# example_led.net
KiCad netlist of a schematic drawn in EAGLE
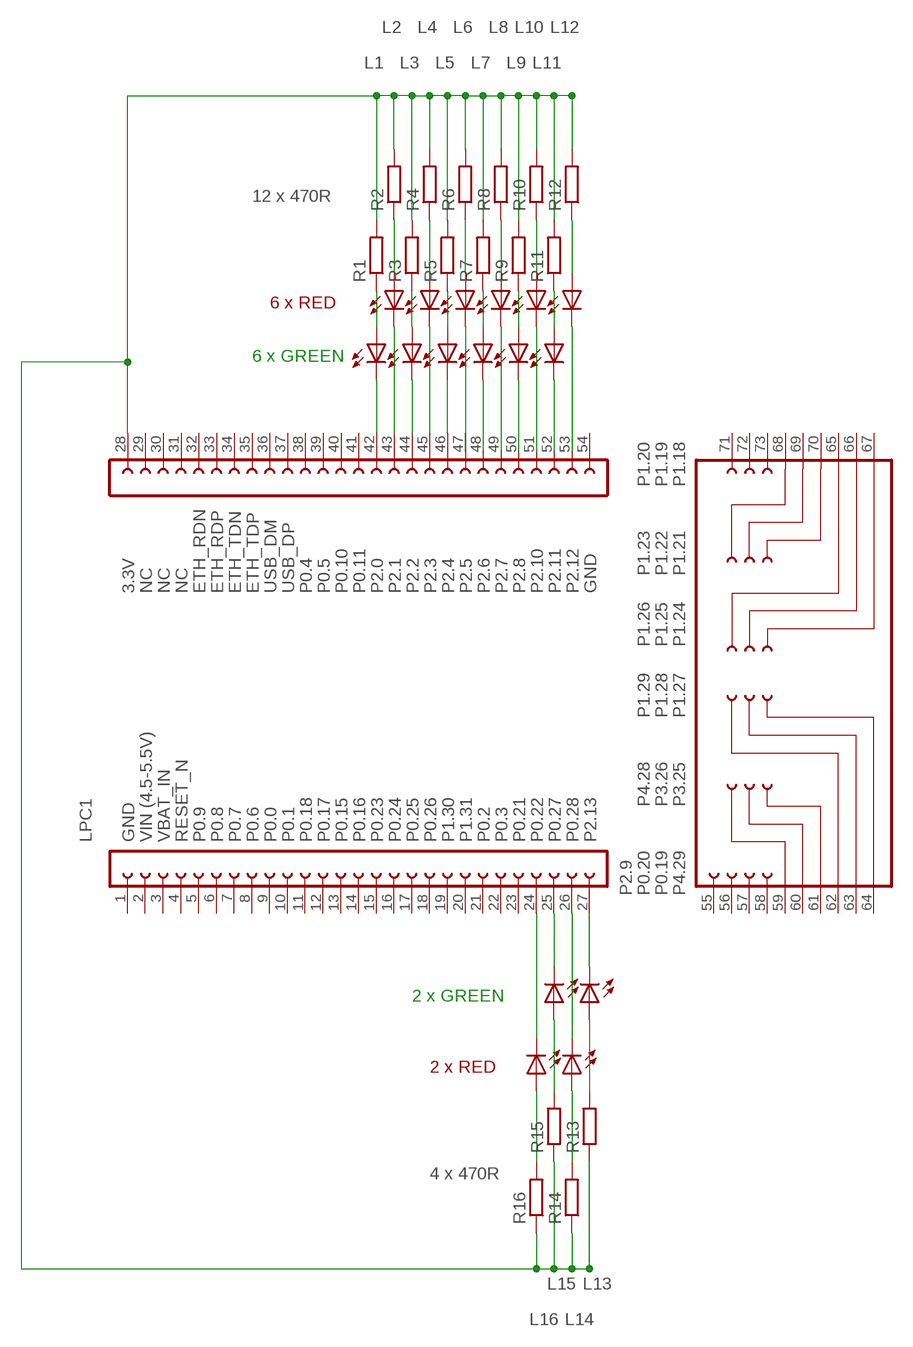
[diagram p0: schematic, sheet 1]

(export (version "E")
  (design (tool "Eeschema 10.0.6"))
  (components
    (comp (ref "L1")
      (value "LRP4-TOP")
      (footprint "eagle-import:P47F-TOP")
      (libsource (lib "eagle-import") (part "P4-TOPLR"))
    )
    (comp (ref "L2")
      (value "LRP4-TOP")
      (footprint "eagle-import:P47F-TOP")
      (libsource (lib "eagle-import") (part "P4-TOPLR"))
    )
    (comp (ref "L3")
      (value "LRP4-TOP")
      (footprint "eagle-import:P47F-TOP")
      (libsource (lib "eagle-import") (part "P4-TOPLR"))
    )
    (comp (ref "L4")
      (value "LRP4-TOP")
      (footprint "eagle-import:P47F-TOP")
      (libsource (lib "eagle-import") (part "P4-TOPLR"))
    )
    (comp (ref "L5")
      (value "LRP4-TOP")
      (footprint "eagle-import:P47F-TOP")
      (libsource (lib "eagle-import") (part "P4-TOPLR"))
    )
    (comp (ref "L6")
      (value "LRP4-TOP")
      (footprint "eagle-import:P47F-TOP")
      (libsource (lib "eagle-import") (part "P4-TOPLR"))
    )
    (comp (ref "L7")
      (value "LRP4-TOP")
      (footprint "eagle-import:P47F-TOP")
      (libsource (lib "eagle-import") (part "P4-TOPLR"))
    )
    (comp (ref "L8")
      (value "LRP4-TOP")
      (footprint "eagle-import:P47F-TOP")
      (libsource (lib "eagle-import") (part "P4-TOPLR"))
    )
    (comp (ref "L9")
      (value "LRP4-TOP")
      (footprint "eagle-import:P47F-TOP")
      (libsource (lib "eagle-import") (part "P4-TOPLR"))
    )
    (comp (ref "L10")
      (value "LRP4-TOP")
      (footprint "eagle-import:P47F-TOP")
      (libsource (lib "eagle-import") (part "P4-TOPLR"))
    )
    (comp (ref "L11")
      (value "LRP4-TOP")
      (footprint "eagle-import:P47F-TOP")
      (libsource (lib "eagle-import") (part "P4-TOPLR"))
    )
    (comp (ref "L12")
      (value "LRP4-TOP")
      (footprint "eagle-import:P47F-TOP")
      (libsource (lib "eagle-import") (part "P4-TOPLR"))
    )
    (comp (ref "L13")
      (value "LRP4-TOP")
      (footprint "eagle-import:P47F-TOP")
      (libsource (lib "eagle-import") (part "P4-TOPLR"))
    )
    (comp (ref "L14")
      (value "LRP4-TOP")
      (footprint "eagle-import:P47F-TOP")
      (libsource (lib "eagle-import") (part "P4-TOPLR"))
    )
    (comp (ref "L15")
      (value "LRP4-TOP")
      (footprint "eagle-import:P47F-TOP")
      (libsource (lib "eagle-import") (part "P4-TOPLR"))
    )
    (comp (ref "L16")
      (value "LRP4-TOP")
      (footprint "eagle-import:P47F-TOP")
      (libsource (lib "eagle-import") (part "P4-TOPLR"))
    )
    (comp (ref "LPC1")
      (value "LPCXPRESSO_LPC1769")
      (footprint "eagle-import:LPCXPRESSO_LPC1769")
      (libsource (lib "eagle-import") (part "LPCXPRESSO_LPC1769"))
    )
    (comp (ref "R1")
      (value "470R")
      (footprint "eagle-import:0204V")
      (libsource (lib "eagle-import") (part "R-EU_0204/2V"))
    )
    (comp (ref "R2")
      (value "470R")
      (footprint "eagle-import:0204V")
      (libsource (lib "eagle-import") (part "R-EU_0204/2V"))
    )
    (comp (ref "R3")
      (value "470R")
      (footprint "eagle-import:0204V")
      (libsource (lib "eagle-import") (part "R-EU_0204/2V"))
    )
    (comp (ref "R4")
      (value "470R")
      (footprint "eagle-import:0204V")
      (libsource (lib "eagle-import") (part "R-EU_0204/2V"))
    )
    (comp (ref "R5")
      (value "470R")
      (footprint "eagle-import:0204V")
      (libsource (lib "eagle-import") (part "R-EU_0204/2V"))
    )
    (comp (ref "R6")
      (value "470R")
      (footprint "eagle-import:0204V")
      (libsource (lib "eagle-import") (part "R-EU_0204/2V"))
    )
    (comp (ref "R7")
      (value "470R")
      (footprint "eagle-import:0204V")
      (libsource (lib "eagle-import") (part "R-EU_0204/2V"))
    )
    (comp (ref "R8")
      (value "470R")
      (footprint "eagle-import:0204V")
      (libsource (lib "eagle-import") (part "R-EU_0204/2V"))
    )
    (comp (ref "R9")
      (value "470R")
      (footprint "eagle-import:0204V")
      (libsource (lib "eagle-import") (part "R-EU_0204/2V"))
    )
    (comp (ref "R10")
      (value "470R")
      (footprint "eagle-import:0204V")
      (libsource (lib "eagle-import") (part "R-EU_0204/2V"))
    )
    (comp (ref "R11")
      (value "470R")
      (footprint "eagle-import:0204V")
      (libsource (lib "eagle-import") (part "R-EU_0204/2V"))
    )
    (comp (ref "R12")
      (value "470R")
      (footprint "eagle-import:0204V")
      (libsource (lib "eagle-import") (part "R-EU_0204/2V"))
    )
    (comp (ref "R13")
      (value "470R")
      (footprint "eagle-import:0204V")
      (libsource (lib "eagle-import") (part "R-EU_0204/2V"))
    )
    (comp (ref "R14")
      (value "470R")
      (footprint "eagle-import:0204V")
      (libsource (lib "eagle-import") (part "R-EU_0204/2V"))
    )
    (comp (ref "R15")
      (value "470R")
      (footprint "eagle-import:0204V")
      (libsource (lib "eagle-import") (part "R-EU_0204/2V"))
    )
    (comp (ref "R16")
      (value "470R")
      (footprint "eagle-import:0204V")
      (libsource (lib "eagle-import") (part "R-EU_0204/2V"))
    )
  )
  (nets
    (net (code "1") (name "Net-(L1-PadA)") (class "Default")
      (node (ref "L1") (pin "A") (pinfunction "A_A") (pintype "passive"))
      (node (ref "R1") (pin "1") (pinfunction "1_1") (pintype "passive"))
    )
    (net (code "2") (name "Net-(L1-PadC)") (class "Default")
      (node (ref "L1") (pin "C") (pinfunction "C_C") (pintype "passive"))
      (node (ref "LPC1") (pin "42") (pinfunction "42_42") (pintype "passive"))
    )
    (net (code "3") (name "Net-(L2-PadA)") (class "Default")
      (node (ref "L2") (pin "A") (pinfunction "A_A") (pintype "passive"))
      (node (ref "R2") (pin "1") (pinfunction "1_1") (pintype "passive"))
    )
    (net (code "4") (name "Net-(L2-PadC)") (class "Default")
      (node (ref "L2") (pin "C") (pinfunction "C_C") (pintype "passive"))
      (node (ref "LPC1") (pin "43") (pinfunction "43_43") (pintype "passive"))
    )
    (net (code "5") (name "Net-(L3-PadA)") (class "Default")
      (node (ref "L3") (pin "A") (pinfunction "A_A") (pintype "passive"))
      (node (ref "R3") (pin "1") (pinfunction "1_1") (pintype "passive"))
    )
    (net (code "6") (name "Net-(L3-PadC)") (class "Default")
      (node (ref "L3") (pin "C") (pinfunction "C_C") (pintype "passive"))
      (node (ref "LPC1") (pin "44") (pinfunction "44_44") (pintype "passive"))
    )
    (net (code "7") (name "Net-(L4-PadA)") (class "Default")
      (node (ref "L4") (pin "A") (pinfunction "A_A") (pintype "passive"))
      (node (ref "R4") (pin "1") (pinfunction "1_1") (pintype "passive"))
    )
    (net (code "8") (name "Net-(L4-PadC)") (class "Default")
      (node (ref "L4") (pin "C") (pinfunction "C_C") (pintype "passive"))
      (node (ref "LPC1") (pin "45") (pinfunction "45_45") (pintype "passive"))
    )
    (net (code "9") (name "Net-(L5-PadA)") (class "Default")
      (node (ref "L5") (pin "A") (pinfunction "A_A") (pintype "passive"))
      (node (ref "R5") (pin "1") (pinfunction "1_1") (pintype "passive"))
    )
    (net (code "10") (name "Net-(L5-PadC)") (class "Default")
      (node (ref "L5") (pin "C") (pinfunction "C_C") (pintype "passive"))
      (node (ref "LPC1") (pin "46") (pinfunction "46_46") (pintype "passive"))
    )
    (net (code "11") (name "Net-(L6-PadA)") (class "Default")
      (node (ref "L6") (pin "A") (pinfunction "A_A") (pintype "passive"))
      (node (ref "R6") (pin "1") (pinfunction "1_1") (pintype "passive"))
    )
    (net (code "12") (name "Net-(L6-PadC)") (class "Default")
      (node (ref "L6") (pin "C") (pinfunction "C_C") (pintype "passive"))
      (node (ref "LPC1") (pin "47") (pinfunction "47_47") (pintype "passive"))
    )
    (net (code "13") (name "Net-(L7-PadA)") (class "Default")
      (node (ref "L7") (pin "A") (pinfunction "A_A") (pintype "passive"))
      (node (ref "R7") (pin "1") (pinfunction "1_1") (pintype "passive"))
    )
    (net (code "14") (name "Net-(L7-PadC)") (class "Default")
      (node (ref "L7") (pin "C") (pinfunction "C_C") (pintype "passive"))
      (node (ref "LPC1") (pin "48") (pinfunction "48_48") (pintype "passive"))
    )
    (net (code "15") (name "Net-(L8-PadA)") (class "Default")
      (node (ref "L8") (pin "A") (pinfunction "A_A") (pintype "passive"))
      (node (ref "R8") (pin "1") (pinfunction "1_1") (pintype "passive"))
    )
    (net (code "16") (name "Net-(L8-PadC)") (class "Default")
      (node (ref "L8") (pin "C") (pinfunction "C_C") (pintype "passive"))
      (node (ref "LPC1") (pin "49") (pinfunction "49_49") (pintype "passive"))
    )
    (net (code "17") (name "Net-(L9-PadA)") (class "Default")
      (node (ref "L9") (pin "A") (pinfunction "A_A") (pintype "passive"))
      (node (ref "R9") (pin "1") (pinfunction "1_1") (pintype "passive"))
    )
    (net (code "18") (name "Net-(L9-PadC)") (class "Default")
      (node (ref "L9") (pin "C") (pinfunction "C_C") (pintype "passive"))
      (node (ref "LPC1") (pin "50") (pinfunction "50_50") (pintype "passive"))
    )
    (net (code "19") (name "Net-(L10-PadA)") (class "Default")
      (node (ref "L10") (pin "A") (pinfunction "A_A") (pintype "passive"))
      (node (ref "R10") (pin "1") (pinfunction "1_1") (pintype "passive"))
    )
    (net (code "20") (name "Net-(L10-PadC)") (class "Default")
      (node (ref "L10") (pin "C") (pinfunction "C_C") (pintype "passive"))
      (node (ref "LPC1") (pin "51") (pinfunction "51_51") (pintype "passive"))
    )
    (net (code "21") (name "Net-(L11-PadA)") (class "Default")
      (node (ref "L11") (pin "A") (pinfunction "A_A") (pintype "passive"))
      (node (ref "R11") (pin "1") (pinfunction "1_1") (pintype "passive"))
    )
    (net (code "22") (name "Net-(L11-PadC)") (class "Default")
      (node (ref "L11") (pin "C") (pinfunction "C_C") (pintype "passive"))
      (node (ref "LPC1") (pin "52") (pinfunction "52_52") (pintype "passive"))
    )
    (net (code "23") (name "Net-(L12-PadA)") (class "Default")
      (node (ref "L12") (pin "A") (pinfunction "A_A") (pintype "passive"))
      (node (ref "R12") (pin "1") (pinfunction "1_1") (pintype "passive"))
    )
    (net (code "24") (name "Net-(L12-PadC)") (class "Default")
      (node (ref "L12") (pin "C") (pinfunction "C_C") (pintype "passive"))
      (node (ref "LPC1") (pin "53") (pinfunction "53_53") (pintype "passive"))
    )
    (net (code "25") (name "Net-(L13-PadA)") (class "Default")
      (node (ref "L13") (pin "A") (pinfunction "A_A") (pintype "passive"))
      (node (ref "R13") (pin "2") (pinfunction "2_2") (pintype "passive"))
    )
    (net (code "26") (name "Net-(L13-PadC)") (class "Default")
      (node (ref "L13") (pin "C") (pinfunction "C_C") (pintype "passive"))
      (node (ref "LPC1") (pin "27") (pinfunction "27_27") (pintype "passive"))
    )
    (net (code "27") (name "Net-(L14-PadA)") (class "Default")
      (node (ref "L14") (pin "A") (pinfunction "A_A") (pintype "passive"))
      (node (ref "R14") (pin "2") (pinfunction "2_2") (pintype "passive"))
    )
    (net (code "28") (name "Net-(L14-PadC)") (class "Default")
      (node (ref "L14") (pin "C") (pinfunction "C_C") (pintype "passive"))
      (node (ref "LPC1") (pin "26") (pinfunction "26_26") (pintype "passive"))
    )
    (net (code "29") (name "Net-(L15-PadA)") (class "Default")
      (node (ref "L15") (pin "A") (pinfunction "A_A") (pintype "passive"))
      (node (ref "R15") (pin "2") (pinfunction "2_2") (pintype "passive"))
    )
    (net (code "30") (name "Net-(L15-PadC)") (class "Default")
      (node (ref "L15") (pin "C") (pinfunction "C_C") (pintype "passive"))
      (node (ref "LPC1") (pin "25") (pinfunction "25_25") (pintype "passive"))
    )
    (net (code "31") (name "Net-(L16-PadA)") (class "Default")
      (node (ref "L16") (pin "A") (pinfunction "A_A") (pintype "passive"))
      (node (ref "R16") (pin "2") (pinfunction "2_2") (pintype "passive"))
    )
    (net (code "32") (name "Net-(L16-PadC)") (class "Default")
      (node (ref "L16") (pin "C") (pinfunction "C_C") (pintype "passive"))
      (node (ref "LPC1") (pin "24") (pinfunction "24_24") (pintype "passive"))
    )
    (net (code "33") (name "Net-(LPC1-Pad28)") (class "Default")
      (node (ref "LPC1") (pin "28") (pinfunction "28_28") (pintype "passive"))
      (node (ref "R1") (pin "2") (pinfunction "2_2") (pintype "passive"))
      (node (ref "R10") (pin "2") (pinfunction "2_2") (pintype "passive"))
      (node (ref "R11") (pin "2") (pinfunction "2_2") (pintype "passive"))
      (node (ref "R12") (pin "2") (pinfunction "2_2") (pintype "passive"))
      (node (ref "R13") (pin "1") (pinfunction "1_1") (pintype "passive"))
      (node (ref "R14") (pin "1") (pinfunction "1_1") (pintype "passive"))
      (node (ref "R15") (pin "1") (pinfunction "1_1") (pintype "passive"))
      (node (ref "R16") (pin "1") (pinfunction "1_1") (pintype "passive"))
      (node (ref "R2") (pin "2") (pinfunction "2_2") (pintype "passive"))
      (node (ref "R3") (pin "2") (pinfunction "2_2") (pintype "passive"))
      (node (ref "R4") (pin "2") (pinfunction "2_2") (pintype "passive"))
      (node (ref "R5") (pin "2") (pinfunction "2_2") (pintype "passive"))
      (node (ref "R6") (pin "2") (pinfunction "2_2") (pintype "passive"))
      (node (ref "R7") (pin "2") (pinfunction "2_2") (pintype "passive"))
      (node (ref "R8") (pin "2") (pinfunction "2_2") (pintype "passive"))
      (node (ref "R9") (pin "2") (pinfunction "2_2") (pintype "passive"))
    )
    (net (code "34") (name "unconnected-(LPC1-Pad1)") (class "Default")
      (node (ref "LPC1") (pin "1") (pinfunction "1_1") (pintype "passive"))
    )
    (net (code "35") (name "unconnected-(LPC1-Pad2)") (class "Default")
      (node (ref "LPC1") (pin "2") (pinfunction "2_2") (pintype "passive"))
    )
    (net (code "36") (name "unconnected-(LPC1-Pad3)") (class "Default")
      (node (ref "LPC1") (pin "3") (pinfunction "3_3") (pintype "passive"))
    )
    (net (code "37") (name "unconnected-(LPC1-Pad4)") (class "Default")
      (node (ref "LPC1") (pin "4") (pinfunction "4_4") (pintype "passive"))
    )
    (net (code "38") (name "unconnected-(LPC1-Pad5)") (class "Default")
      (node (ref "LPC1") (pin "5") (pinfunction "5_5") (pintype "passive"))
    )
    (net (code "39") (name "unconnected-(LPC1-Pad6)") (class "Default")
      (node (ref "LPC1") (pin "6") (pinfunction "6_6") (pintype "passive"))
    )
    (net (code "40") (name "unconnected-(LPC1-Pad7)") (class "Default")
      (node (ref "LPC1") (pin "7") (pinfunction "7_7") (pintype "passive"))
    )
    (net (code "41") (name "unconnected-(LPC1-Pad8)") (class "Default")
      (node (ref "LPC1") (pin "8") (pinfunction "8_8") (pintype "passive"))
    )
    (net (code "42") (name "unconnected-(LPC1-Pad9)") (class "Default")
      (node (ref "LPC1") (pin "9") (pinfunction "9_9") (pintype "passive"))
    )
    (net (code "43") (name "unconnected-(LPC1-Pad10)") (class "Default")
      (node (ref "LPC1") (pin "10") (pinfunction "10_10") (pintype "passive"))
    )
    (net (code "44") (name "unconnected-(LPC1-Pad11)") (class "Default")
      (node (ref "LPC1") (pin "11") (pinfunction "11_11") (pintype "passive"))
    )
    (net (code "45") (name "unconnected-(LPC1-Pad12)") (class "Default")
      (node (ref "LPC1") (pin "12") (pinfunction "12_12") (pintype "passive"))
    )
    (net (code "46") (name "unconnected-(LPC1-Pad13)") (class "Default")
      (node (ref "LPC1") (pin "13") (pinfunction "13_13") (pintype "passive"))
    )
    (net (code "47") (name "unconnected-(LPC1-Pad14)") (class "Default")
      (node (ref "LPC1") (pin "14") (pinfunction "14_14") (pintype "passive"))
    )
    (net (code "48") (name "unconnected-(LPC1-Pad15)") (class "Default")
      (node (ref "LPC1") (pin "15") (pinfunction "15_15") (pintype "passive"))
    )
    (net (code "49") (name "unconnected-(LPC1-Pad16)") (class "Default")
      (node (ref "LPC1") (pin "16") (pinfunction "16_16") (pintype "passive"))
    )
    (net (code "50") (name "unconnected-(LPC1-Pad17)") (class "Default")
      (node (ref "LPC1") (pin "17") (pinfunction "17_17") (pintype "passive"))
    )
    (net (code "51") (name "unconnected-(LPC1-Pad18)") (class "Default")
      (node (ref "LPC1") (pin "18") (pinfunction "18_18") (pintype "passive"))
    )
    (net (code "52") (name "unconnected-(LPC1-Pad19)") (class "Default")
      (node (ref "LPC1") (pin "19") (pinfunction "19_19") (pintype "passive"))
    )
    (net (code "53") (name "unconnected-(LPC1-Pad20)") (class "Default")
      (node (ref "LPC1") (pin "20") (pinfunction "20_20") (pintype "passive"))
    )
    (net (code "54") (name "unconnected-(LPC1-Pad21)") (class "Default")
      (node (ref "LPC1") (pin "21") (pinfunction "21_21") (pintype "passive"))
    )
    (net (code "55") (name "unconnected-(LPC1-Pad22)") (class "Default")
      (node (ref "LPC1") (pin "22") (pinfunction "22_22") (pintype "passive"))
    )
    (net (code "56") (name "unconnected-(LPC1-Pad23)") (class "Default")
      (node (ref "LPC1") (pin "23") (pinfunction "23_23") (pintype "passive"))
    )
    (net (code "57") (name "unconnected-(LPC1-Pad29)") (class "Default")
      (node (ref "LPC1") (pin "29") (pinfunction "29_29") (pintype "passive"))
    )
    (net (code "58") (name "unconnected-(LPC1-Pad30)") (class "Default")
      (node (ref "LPC1") (pin "30") (pinfunction "30_30") (pintype "passive"))
    )
    (net (code "59") (name "unconnected-(LPC1-Pad31)") (class "Default")
      (node (ref "LPC1") (pin "31") (pinfunction "31_31") (pintype "passive"))
    )
    (net (code "60") (name "unconnected-(LPC1-Pad32)") (class "Default")
      (node (ref "LPC1") (pin "32") (pinfunction "32_32") (pintype "passive"))
    )
    (net (code "61") (name "unconnected-(LPC1-Pad33)") (class "Default")
      (node (ref "LPC1") (pin "33") (pinfunction "33_33") (pintype "passive"))
    )
    (net (code "62") (name "unconnected-(LPC1-Pad34)") (class "Default")
      (node (ref "LPC1") (pin "34") (pinfunction "34_34") (pintype "passive"))
    )
    (net (code "63") (name "unconnected-(LPC1-Pad35)") (class "Default")
      (node (ref "LPC1") (pin "35") (pinfunction "35_35") (pintype "passive"))
    )
    (net (code "64") (name "unconnected-(LPC1-Pad36)") (class "Default")
      (node (ref "LPC1") (pin "36") (pinfunction "36_36") (pintype "passive"))
    )
    (net (code "65") (name "unconnected-(LPC1-Pad37)") (class "Default")
      (node (ref "LPC1") (pin "37") (pinfunction "37_37") (pintype "passive"))
    )
    (net (code "66") (name "unconnected-(LPC1-Pad38)") (class "Default")
      (node (ref "LPC1") (pin "38") (pinfunction "38_38") (pintype "passive"))
    )
    (net (code "67") (name "unconnected-(LPC1-Pad39)") (class "Default")
      (node (ref "LPC1") (pin "39") (pinfunction "39_39") (pintype "passive"))
    )
    (net (code "68") (name "unconnected-(LPC1-Pad40)") (class "Default")
      (node (ref "LPC1") (pin "40") (pinfunction "40_40") (pintype "passive"))
    )
    (net (code "69") (name "unconnected-(LPC1-Pad41)") (class "Default")
      (node (ref "LPC1") (pin "41") (pinfunction "41_41") (pintype "passive"))
    )
    (net (code "70") (name "unconnected-(LPC1-Pad54)") (class "Default")
      (node (ref "LPC1") (pin "54") (pinfunction "54_54") (pintype "passive"))
    )
    (net (code "71") (name "unconnected-(LPC1-Pad55)") (class "Default")
      (node (ref "LPC1") (pin "55") (pinfunction "55_55") (pintype "passive"))
    )
    (net (code "72") (name "unconnected-(LPC1-Pad56)") (class "Default")
      (node (ref "LPC1") (pin "56") (pinfunction "56_56") (pintype "passive"))
    )
    (net (code "73") (name "unconnected-(LPC1-Pad57)") (class "Default")
      (node (ref "LPC1") (pin "57") (pinfunction "57_57") (pintype "passive"))
    )
    (net (code "74") (name "unconnected-(LPC1-Pad58)") (class "Default")
      (node (ref "LPC1") (pin "58") (pinfunction "58_58") (pintype "passive"))
    )
    (net (code "75") (name "unconnected-(LPC1-Pad59)") (class "Default")
      (node (ref "LPC1") (pin "59") (pinfunction "59_59") (pintype "passive"))
    )
    (net (code "76") (name "unconnected-(LPC1-Pad60)") (class "Default")
      (node (ref "LPC1") (pin "60") (pinfunction "60_60") (pintype "passive"))
    )
    (net (code "77") (name "unconnected-(LPC1-Pad61)") (class "Default")
      (node (ref "LPC1") (pin "61") (pinfunction "61_61") (pintype "passive"))
    )
    (net (code "78") (name "unconnected-(LPC1-Pad62)") (class "Default")
      (node (ref "LPC1") (pin "62") (pinfunction "62_62") (pintype "passive"))
    )
    (net (code "79") (name "unconnected-(LPC1-Pad63)") (class "Default")
      (node (ref "LPC1") (pin "63") (pinfunction "63_63") (pintype "passive"))
    )
    (net (code "80") (name "unconnected-(LPC1-Pad64)") (class "Default")
      (node (ref "LPC1") (pin "64") (pinfunction "64_64") (pintype "passive"))
    )
    (net (code "81") (name "unconnected-(LPC1-Pad65)") (class "Default")
      (node (ref "LPC1") (pin "65") (pinfunction "65_65") (pintype "passive"))
    )
    (net (code "82") (name "unconnected-(LPC1-Pad66)") (class "Default")
      (node (ref "LPC1") (pin "66") (pinfunction "66_66") (pintype "passive"))
    )
    (net (code "83") (name "unconnected-(LPC1-Pad67)") (class "Default")
      (node (ref "LPC1") (pin "67") (pinfunction "67_67") (pintype "passive"))
    )
    (net (code "84") (name "unconnected-(LPC1-Pad68)") (class "Default")
      (node (ref "LPC1") (pin "68") (pinfunction "68_68") (pintype "passive"))
    )
    (net (code "85") (name "unconnected-(LPC1-Pad69)") (class "Default")
      (node (ref "LPC1") (pin "69") (pinfunction "69_69") (pintype "passive"))
    )
    (net (code "86") (name "unconnected-(LPC1-Pad70)") (class "Default")
      (node (ref "LPC1") (pin "70") (pinfunction "70_70") (pintype "passive"))
    )
    (net (code "87") (name "unconnected-(LPC1-Pad71)") (class "Default")
      (node (ref "LPC1") (pin "71") (pinfunction "71_71") (pintype "passive"))
    )
    (net (code "88") (name "unconnected-(LPC1-Pad72)") (class "Default")
      (node (ref "LPC1") (pin "72") (pinfunction "72_72") (pintype "passive"))
    )
    (net (code "89") (name "unconnected-(LPC1-Pad73)") (class "Default")
      (node (ref "LPC1") (pin "73") (pinfunction "73_73") (pintype "passive"))
    )
  )
)
